# Capacitive.net
KiCad netlist of a schematic drawn in EAGLE
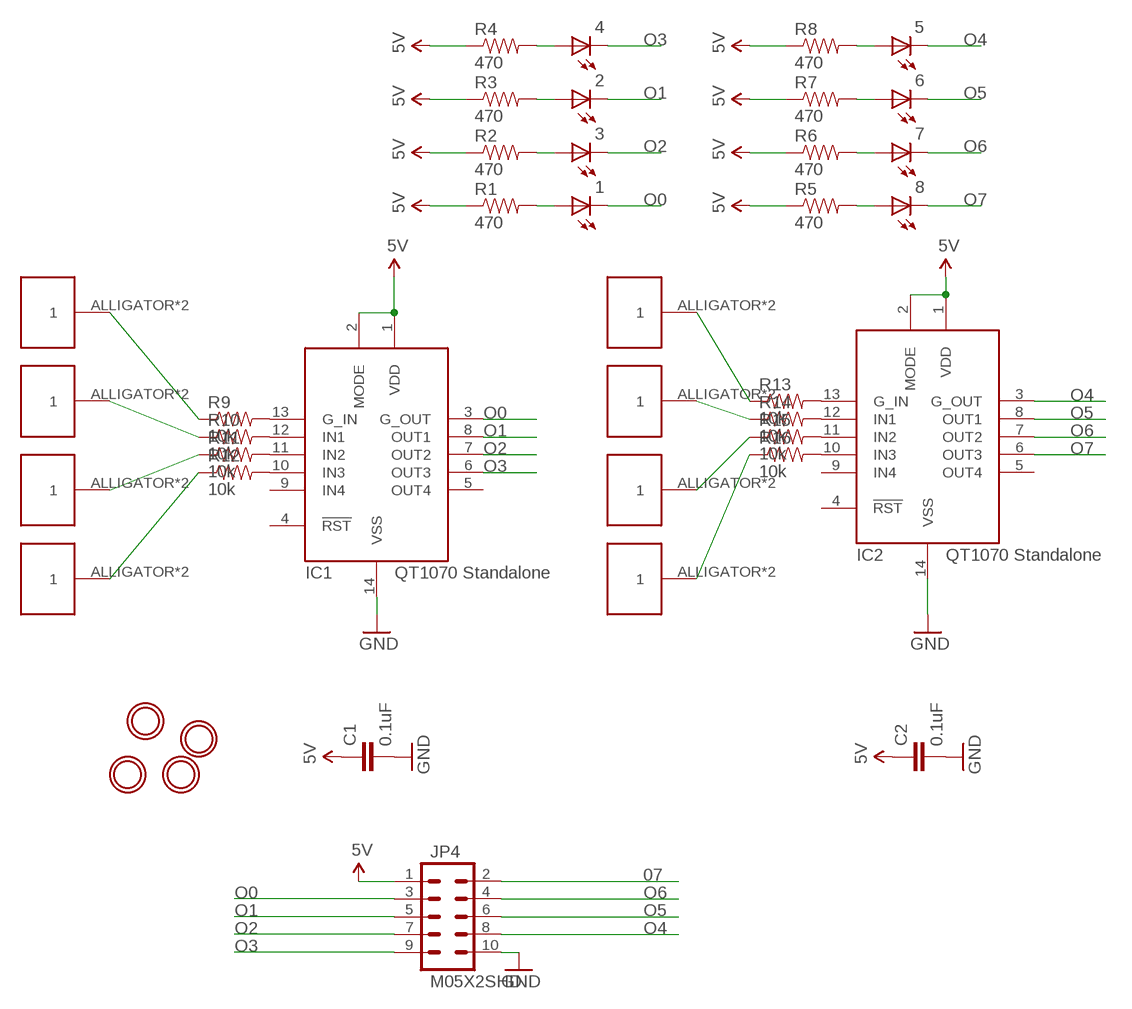
[diagram p0: schematic, sheet 1]

(export (version "E")
  (design (tool "Eeschema 10.0.6"))
  (components
    (comp (ref "1")
      (value "LEDCHIPLED_0805")
      (footprint "eagle-import:CHIPLED_0805")
      (libsource (lib "eagle-import") (part "LEDCHIPLED_0805"))
    )
    (comp (ref "2")
      (value "LEDCHIPLED_0805")
      (footprint "eagle-import:CHIPLED_0805")
      (libsource (lib "eagle-import") (part "LEDCHIPLED_0805"))
    )
    (comp (ref "3")
      (value "LEDCHIPLED_0805")
      (footprint "eagle-import:CHIPLED_0805")
      (libsource (lib "eagle-import") (part "LEDCHIPLED_0805"))
    )
    (comp (ref "4")
      (value "LEDCHIPLED_0805")
      (footprint "eagle-import:CHIPLED_0805")
      (libsource (lib "eagle-import") (part "LEDCHIPLED_0805"))
    )
    (comp (ref "5")
      (value "LEDCHIPLED_0805")
      (footprint "eagle-import:CHIPLED_0805")
      (libsource (lib "eagle-import") (part "LEDCHIPLED_0805"))
    )
    (comp (ref "6")
      (value "LEDCHIPLED_0805")
      (footprint "eagle-import:CHIPLED_0805")
      (libsource (lib "eagle-import") (part "LEDCHIPLED_0805"))
    )
    (comp (ref "7")
      (value "LEDCHIPLED_0805")
      (footprint "eagle-import:CHIPLED_0805")
      (libsource (lib "eagle-import") (part "LEDCHIPLED_0805"))
    )
    (comp (ref "8")
      (value "LEDCHIPLED_0805")
      (footprint "eagle-import:CHIPLED_0805")
      (libsource (lib "eagle-import") (part "LEDCHIPLED_0805"))
    )
    (comp (ref "C1")
      (value "0.1uF")
      (footprint "eagle-import:0805")
      (libsource (lib "eagle-import") (part "CAP0805"))
    )
    (comp (ref "C2")
      (value "0.1uF")
      (footprint "eagle-import:0805")
      (libsource (lib "eagle-import") (part "CAP0805"))
    )
    (comp (ref "IC1")
      (value "AT42QT1070")
      (footprint "eagle-import:SO14")
      (libsource (lib "eagle-import") (part "AT42QT1070-SSU"))
    )
    (comp (ref "IC2")
      (value "AT42QT1070")
      (footprint "eagle-import:SO14")
      (libsource (lib "eagle-import") (part "AT42QT1070-SSU"))
    )
    (comp (ref "JP4")
      (value "M05X2SHD")
      (footprint "eagle-import:2X5-SHROUDED")
      (libsource (lib "eagle-import") (part "M05X2SHD"))
    )
    (comp (ref "R1")
      (value "470")
      (footprint "eagle-import:0805")
      (libsource (lib "eagle-import") (part "RESISTOR0805-RES"))
    )
    (comp (ref "R2")
      (value "470")
      (footprint "eagle-import:0805")
      (libsource (lib "eagle-import") (part "RESISTOR0805-RES"))
    )
    (comp (ref "R3")
      (value "470")
      (footprint "eagle-import:0805")
      (libsource (lib "eagle-import") (part "RESISTOR0805-RES"))
    )
    (comp (ref "R4")
      (value "470")
      (footprint "eagle-import:0805")
      (libsource (lib "eagle-import") (part "RESISTOR0805-RES"))
    )
    (comp (ref "R5")
      (value "470")
      (footprint "eagle-import:0805")
      (libsource (lib "eagle-import") (part "RESISTOR0805-RES"))
    )
    (comp (ref "R6")
      (value "470")
      (footprint "eagle-import:0805")
      (libsource (lib "eagle-import") (part "RESISTOR0805-RES"))
    )
    (comp (ref "R7")
      (value "470")
      (footprint "eagle-import:0805")
      (libsource (lib "eagle-import") (part "RESISTOR0805-RES"))
    )
    (comp (ref "R8")
      (value "470")
      (footprint "eagle-import:0805")
      (libsource (lib "eagle-import") (part "RESISTOR0805-RES"))
    )
    (comp (ref "R9")
      (value "10k")
      (footprint "eagle-import:0805")
      (libsource (lib "eagle-import") (part "RESISTOR0805-RES"))
    )
    (comp (ref "R10")
      (value "10k")
      (footprint "eagle-import:0805")
      (libsource (lib "eagle-import") (part "RESISTOR0805-RES"))
    )
    (comp (ref "R11")
      (value "10k")
      (footprint "eagle-import:0805")
      (libsource (lib "eagle-import") (part "RESISTOR0805-RES"))
    )
    (comp (ref "R12")
      (value "10k")
      (footprint "eagle-import:0805")
      (libsource (lib "eagle-import") (part "RESISTOR0805-RES"))
    )
    (comp (ref "R13")
      (value "10k")
      (footprint "eagle-import:0805")
      (libsource (lib "eagle-import") (part "RESISTOR0805-RES"))
    )
    (comp (ref "R14")
      (value "10k")
      (footprint "eagle-import:0805")
      (libsource (lib "eagle-import") (part "RESISTOR0805-RES"))
    )
    (comp (ref "R15")
      (value "10k")
      (footprint "eagle-import:0805")
      (libsource (lib "eagle-import") (part "RESISTOR0805-RES"))
    )
    (comp (ref "R16")
      (value "10k")
      (footprint "eagle-import:0805")
      (libsource (lib "eagle-import") (part "RESISTOR0805-RES"))
    )
    (comp (ref "U$1")
      (value "ALLIGATOR_CONN")
      (footprint "eagle-import:3MM_ALLIGATOR")
      (libsource (lib "eagle-import") (part "ALLIGATOR_CONN"))
    )
    (comp (ref "U$2")
      (value "ALLIGATOR_CONN")
      (footprint "eagle-import:3MM_ALLIGATOR")
      (libsource (lib "eagle-import") (part "ALLIGATOR_CONN"))
    )
    (comp (ref "U$3")
      (value "ALLIGATOR_CONN")
      (footprint "eagle-import:3MM_ALLIGATOR")
      (libsource (lib "eagle-import") (part "ALLIGATOR_CONN"))
    )
    (comp (ref "U$4")
      (value "ALLIGATOR_CONN")
      (footprint "eagle-import:3MM_ALLIGATOR")
      (libsource (lib "eagle-import") (part "ALLIGATOR_CONN"))
    )
    (comp (ref "U$5")
      (value "ALLIGATOR_CONN")
      (footprint "eagle-import:3MM_ALLIGATOR")
      (libsource (lib "eagle-import") (part "ALLIGATOR_CONN"))
    )
    (comp (ref "U$6")
      (value "ALLIGATOR_CONN")
      (footprint "eagle-import:3MM_ALLIGATOR")
      (libsource (lib "eagle-import") (part "ALLIGATOR_CONN"))
    )
    (comp (ref "U$7")
      (value "ALLIGATOR_CONN")
      (footprint "eagle-import:3MM_ALLIGATOR")
      (libsource (lib "eagle-import") (part "ALLIGATOR_CONN"))
    )
    (comp (ref "U$8")
      (value "ALLIGATOR_CONN")
      (footprint "eagle-import:3MM_ALLIGATOR")
      (libsource (lib "eagle-import") (part "ALLIGATOR_CONN"))
    )
    (comp (ref "U$9")
      (value "MOUNTINGHOLE2.0")
      (footprint "eagle-import:MOUNTINGHOLE_2.0_PLATED")
      (libsource (lib "eagle-import") (part "MOUNTINGHOLE2.0"))
    )
    (comp (ref "U$10")
      (value "MOUNTINGHOLE2.0")
      (footprint "eagle-import:MOUNTINGHOLE_2.0_PLATED")
      (libsource (lib "eagle-import") (part "MOUNTINGHOLE2.0"))
    )
    (comp (ref "U$11")
      (value "MOUNTINGHOLE2.0")
      (footprint "eagle-import:MOUNTINGHOLE_2.0_PLATED")
      (libsource (lib "eagle-import") (part "MOUNTINGHOLE2.0"))
    )
    (comp (ref "U$12")
      (value "MOUNTINGHOLE2.0")
      (footprint "eagle-import:MOUNTINGHOLE_2.0_PLATED")
      (libsource (lib "eagle-import") (part "MOUNTINGHOLE2.0"))
    )
  )
  (nets
    (net (code "1") (name "/07") (class "Default")
      (node (ref "JP4") (pin "2") (pinfunction "2_2") (pintype "passive"))
    )
    (net (code "2") (name "/O0") (class "Default")
      (node (ref "1") (pin "C") (pinfunction "C_C") (pintype "passive"))
      (node (ref "IC1") (pin "3") (pinfunction "G_OUT_3") (pintype "open_collector"))
      (node (ref "JP4") (pin "3") (pinfunction "3_3") (pintype "passive"))
    )
    (net (code "3") (name "/O1") (class "Default")
      (node (ref "2") (pin "C") (pinfunction "C_C") (pintype "passive"))
      (node (ref "IC1") (pin "8") (pinfunction "OUT1_8") (pintype "open_collector"))
      (node (ref "JP4") (pin "5") (pinfunction "5_5") (pintype "passive"))
    )
    (net (code "4") (name "/O2") (class "Default")
      (node (ref "3") (pin "C") (pinfunction "C_C") (pintype "passive"))
      (node (ref "IC1") (pin "7") (pinfunction "OUT2_7") (pintype "open_collector"))
      (node (ref "JP4") (pin "7") (pinfunction "7_7") (pintype "passive"))
    )
    (net (code "5") (name "/O3") (class "Default")
      (node (ref "4") (pin "C") (pinfunction "C_C") (pintype "passive"))
      (node (ref "IC1") (pin "6") (pinfunction "OUT3_6") (pintype "open_collector"))
      (node (ref "JP4") (pin "9") (pinfunction "9_9") (pintype "passive"))
    )
    (net (code "6") (name "/O4") (class "Default")
      (node (ref "5") (pin "C") (pinfunction "C_C") (pintype "passive"))
      (node (ref "IC2") (pin "3") (pinfunction "G_OUT_3") (pintype "open_collector"))
      (node (ref "JP4") (pin "8") (pinfunction "8_8") (pintype "passive"))
    )
    (net (code "7") (name "/O5") (class "Default")
      (node (ref "6") (pin "C") (pinfunction "C_C") (pintype "passive"))
      (node (ref "IC2") (pin "8") (pinfunction "OUT1_8") (pintype "open_collector"))
      (node (ref "JP4") (pin "6") (pinfunction "6_6") (pintype "passive"))
    )
    (net (code "8") (name "/O6") (class "Default")
      (node (ref "7") (pin "C") (pinfunction "C_C") (pintype "passive"))
      (node (ref "IC2") (pin "7") (pinfunction "OUT2_7") (pintype "open_collector"))
      (node (ref "JP4") (pin "4") (pinfunction "4_4") (pintype "passive"))
    )
    (net (code "9") (name "/O7") (class "Default")
      (node (ref "8") (pin "C") (pinfunction "C_C") (pintype "passive"))
      (node (ref "IC2") (pin "6") (pinfunction "OUT3_6") (pintype "open_collector"))
    )
    (net (code "10") (name "5V") (class "Default")
      (node (ref "C1") (pin "1") (pinfunction "1_1") (pintype "passive"))
      (node (ref "C2") (pin "1") (pinfunction "1_1") (pintype "passive"))
      (node (ref "IC1") (pin "1") (pinfunction "VDD_1") (pintype "power_in"))
      (node (ref "IC1") (pin "2") (pinfunction "MODE_2") (pintype "input"))
      (node (ref "IC2") (pin "1") (pinfunction "VDD_1") (pintype "power_in"))
      (node (ref "IC2") (pin "2") (pinfunction "MODE_2") (pintype "input"))
      (node (ref "JP4") (pin "1") (pinfunction "1_1") (pintype "passive"))
      (node (ref "R1") (pin "1") (pinfunction "1_1") (pintype "passive"))
      (node (ref "R2") (pin "1") (pinfunction "1_1") (pintype "passive"))
      (node (ref "R3") (pin "1") (pinfunction "1_1") (pintype "passive"))
      (node (ref "R4") (pin "1") (pinfunction "1_1") (pintype "passive"))
      (node (ref "R5") (pin "1") (pinfunction "1_1") (pintype "passive"))
      (node (ref "R6") (pin "1") (pinfunction "1_1") (pintype "passive"))
      (node (ref "R7") (pin "1") (pinfunction "1_1") (pintype "passive"))
      (node (ref "R8") (pin "1") (pinfunction "1_1") (pintype "passive"))
    )
    (net (code "11") (name "GND") (class "Default")
      (node (ref "C1") (pin "2") (pinfunction "2_2") (pintype "passive"))
      (node (ref "C2") (pin "2") (pinfunction "2_2") (pintype "passive"))
      (node (ref "IC1") (pin "14") (pinfunction "VSS_14") (pintype "power_in"))
      (node (ref "IC2") (pin "14") (pinfunction "VSS_14") (pintype "power_in"))
      (node (ref "JP4") (pin "10") (pinfunction "10_10") (pintype "passive"))
    )
    (net (code "12") (name "Net-(1-PadA)") (class "Default")
      (node (ref "1") (pin "A") (pinfunction "A_A") (pintype "passive"))
      (node (ref "R1") (pin "2") (pinfunction "2_2") (pintype "passive"))
    )
    (net (code "13") (name "Net-(2-PadA)") (class "Default")
      (node (ref "2") (pin "A") (pinfunction "A_A") (pintype "passive"))
      (node (ref "R3") (pin "2") (pinfunction "2_2") (pintype "passive"))
    )
    (net (code "14") (name "Net-(3-PadA)") (class "Default")
      (node (ref "3") (pin "A") (pinfunction "A_A") (pintype "passive"))
      (node (ref "R2") (pin "2") (pinfunction "2_2") (pintype "passive"))
    )
    (net (code "15") (name "Net-(4-PadA)") (class "Default")
      (node (ref "4") (pin "A") (pinfunction "A_A") (pintype "passive"))
      (node (ref "R4") (pin "2") (pinfunction "2_2") (pintype "passive"))
    )
    (net (code "16") (name "Net-(5-PadA)") (class "Default")
      (node (ref "5") (pin "A") (pinfunction "A_A") (pintype "passive"))
      (node (ref "R8") (pin "2") (pinfunction "2_2") (pintype "passive"))
    )
    (net (code "17") (name "Net-(6-PadA)") (class "Default")
      (node (ref "6") (pin "A") (pinfunction "A_A") (pintype "passive"))
      (node (ref "R7") (pin "2") (pinfunction "2_2") (pintype "passive"))
    )
    (net (code "18") (name "Net-(7-PadA)") (class "Default")
      (node (ref "7") (pin "A") (pinfunction "A_A") (pintype "passive"))
      (node (ref "R6") (pin "2") (pinfunction "2_2") (pintype "passive"))
    )
    (net (code "19") (name "Net-(8-PadA)") (class "Default")
      (node (ref "8") (pin "A") (pinfunction "A_A") (pintype "passive"))
      (node (ref "R5") (pin "2") (pinfunction "2_2") (pintype "passive"))
    )
    (net (code "20") (name "Net-(IC1-G_IN)") (class "Default")
      (node (ref "IC1") (pin "13") (pinfunction "G_IN_13") (pintype "input"))
      (node (ref "R9") (pin "2") (pinfunction "2_2") (pintype "passive"))
    )
    (net (code "21") (name "Net-(IC1-IN1)") (class "Default")
      (node (ref "IC1") (pin "12") (pinfunction "IN1_12") (pintype "input"))
      (node (ref "R10") (pin "2") (pinfunction "2_2") (pintype "passive"))
    )
    (net (code "22") (name "Net-(IC1-IN2)") (class "Default")
      (node (ref "IC1") (pin "11") (pinfunction "IN2_11") (pintype "input"))
      (node (ref "R11") (pin "2") (pinfunction "2_2") (pintype "passive"))
    )
    (net (code "23") (name "Net-(IC1-IN3)") (class "Default")
      (node (ref "IC1") (pin "10") (pinfunction "IN3_10") (pintype "input"))
      (node (ref "R12") (pin "2") (pinfunction "2_2") (pintype "passive"))
    )
    (net (code "24") (name "Net-(IC2-G_IN)") (class "Default")
      (node (ref "IC2") (pin "13") (pinfunction "G_IN_13") (pintype "input"))
      (node (ref "R13") (pin "2") (pinfunction "2_2") (pintype "passive"))
    )
    (net (code "25") (name "Net-(IC2-IN1)") (class "Default")
      (node (ref "IC2") (pin "12") (pinfunction "IN1_12") (pintype "input"))
      (node (ref "R14") (pin "2") (pinfunction "2_2") (pintype "passive"))
    )
    (net (code "26") (name "Net-(IC2-IN2)") (class "Default")
      (node (ref "IC2") (pin "11") (pinfunction "IN2_11") (pintype "input"))
      (node (ref "R15") (pin "2") (pinfunction "2_2") (pintype "passive"))
    )
    (net (code "27") (name "Net-(IC2-IN3)") (class "Default")
      (node (ref "IC2") (pin "10") (pinfunction "IN3_10") (pintype "input"))
      (node (ref "R16") (pin "2") (pinfunction "2_2") (pintype "passive"))
    )
    (net (code "28") (name "Net-(R9-Pad1)") (class "Default")
      (node (ref "R9") (pin "1") (pinfunction "1_1") (pintype "passive"))
      (node (ref "U$1") (pin "ALLIGATOR") (pinfunction "1_ALLIGATOR") (pintype "bidirectional"))
      (node (ref "U$1") (pin "ALLIGATOR1") (pinfunction "1_ALLIGATOR1") (pintype "bidirectional"))
    )
    (net (code "29") (name "Net-(R10-Pad1)") (class "Default")
      (node (ref "R10") (pin "1") (pinfunction "1_1") (pintype "passive"))
      (node (ref "U$2") (pin "ALLIGATOR") (pinfunction "1_ALLIGATOR") (pintype "bidirectional"))
      (node (ref "U$2") (pin "ALLIGATOR1") (pinfunction "1_ALLIGATOR1") (pintype "bidirectional"))
    )
    (net (code "30") (name "Net-(R11-Pad1)") (class "Default")
      (node (ref "R11") (pin "1") (pinfunction "1_1") (pintype "passive"))
      (node (ref "U$3") (pin "ALLIGATOR") (pinfunction "1_ALLIGATOR") (pintype "bidirectional"))
      (node (ref "U$3") (pin "ALLIGATOR1") (pinfunction "1_ALLIGATOR1") (pintype "bidirectional"))
    )
    (net (code "31") (name "Net-(R12-Pad1)") (class "Default")
      (node (ref "R12") (pin "1") (pinfunction "1_1") (pintype "passive"))
      (node (ref "U$4") (pin "ALLIGATOR") (pinfunction "1_ALLIGATOR") (pintype "bidirectional"))
      (node (ref "U$4") (pin "ALLIGATOR1") (pinfunction "1_ALLIGATOR1") (pintype "bidirectional"))
    )
    (net (code "32") (name "Net-(R13-Pad1)") (class "Default")
      (node (ref "R13") (pin "1") (pinfunction "1_1") (pintype "passive"))
      (node (ref "U$5") (pin "ALLIGATOR") (pinfunction "1_ALLIGATOR") (pintype "bidirectional"))
      (node (ref "U$5") (pin "ALLIGATOR1") (pinfunction "1_ALLIGATOR1") (pintype "bidirectional"))
    )
    (net (code "33") (name "Net-(R14-Pad1)") (class "Default")
      (node (ref "R14") (pin "1") (pinfunction "1_1") (pintype "passive"))
      (node (ref "U$6") (pin "ALLIGATOR") (pinfunction "1_ALLIGATOR") (pintype "bidirectional"))
      (node (ref "U$6") (pin "ALLIGATOR1") (pinfunction "1_ALLIGATOR1") (pintype "bidirectional"))
    )
    (net (code "34") (name "Net-(R15-Pad1)") (class "Default")
      (node (ref "R15") (pin "1") (pinfunction "1_1") (pintype "passive"))
      (node (ref "U$7") (pin "ALLIGATOR") (pinfunction "1_ALLIGATOR") (pintype "bidirectional"))
      (node (ref "U$7") (pin "ALLIGATOR1") (pinfunction "1_ALLIGATOR1") (pintype "bidirectional"))
    )
    (net (code "35") (name "Net-(R16-Pad1)") (class "Default")
      (node (ref "R16") (pin "1") (pinfunction "1_1") (pintype "passive"))
      (node (ref "U$8") (pin "ALLIGATOR") (pinfunction "1_ALLIGATOR") (pintype "bidirectional"))
      (node (ref "U$8") (pin "ALLIGATOR1") (pinfunction "1_ALLIGATOR1") (pintype "bidirectional"))
    )
    (net (code "36") (name "unconnected-(IC1-IN4-Pad9)") (class "Default")
      (node (ref "IC1") (pin "9") (pinfunction "IN4_9") (pintype "input"))
    )
    (net (code "37") (name "unconnected-(IC1-OUT4-Pad5)") (class "Default")
      (node (ref "IC1") (pin "5") (pinfunction "OUT4_5") (pintype "open_collector"))
    )
    (net (code "38") (name "unconnected-(IC1-~{RST}-Pad4)") (class "Default")
      (node (ref "IC1") (pin "4") (pinfunction "~{RST}_4") (pintype "input"))
    )
    (net (code "39") (name "unconnected-(IC2-IN4-Pad9)") (class "Default")
      (node (ref "IC2") (pin "9") (pinfunction "IN4_9") (pintype "input"))
    )
    (net (code "40") (name "unconnected-(IC2-OUT4-Pad5)") (class "Default")
      (node (ref "IC2") (pin "5") (pinfunction "OUT4_5") (pintype "open_collector"))
    )
    (net (code "41") (name "unconnected-(IC2-~{RST}-Pad4)") (class "Default")
      (node (ref "IC2") (pin "4") (pinfunction "~{RST}_4") (pintype "input"))
    )
  )
)
